# TMS320F28335.net
KiCad netlist of a schematic drawn in Altium Designer
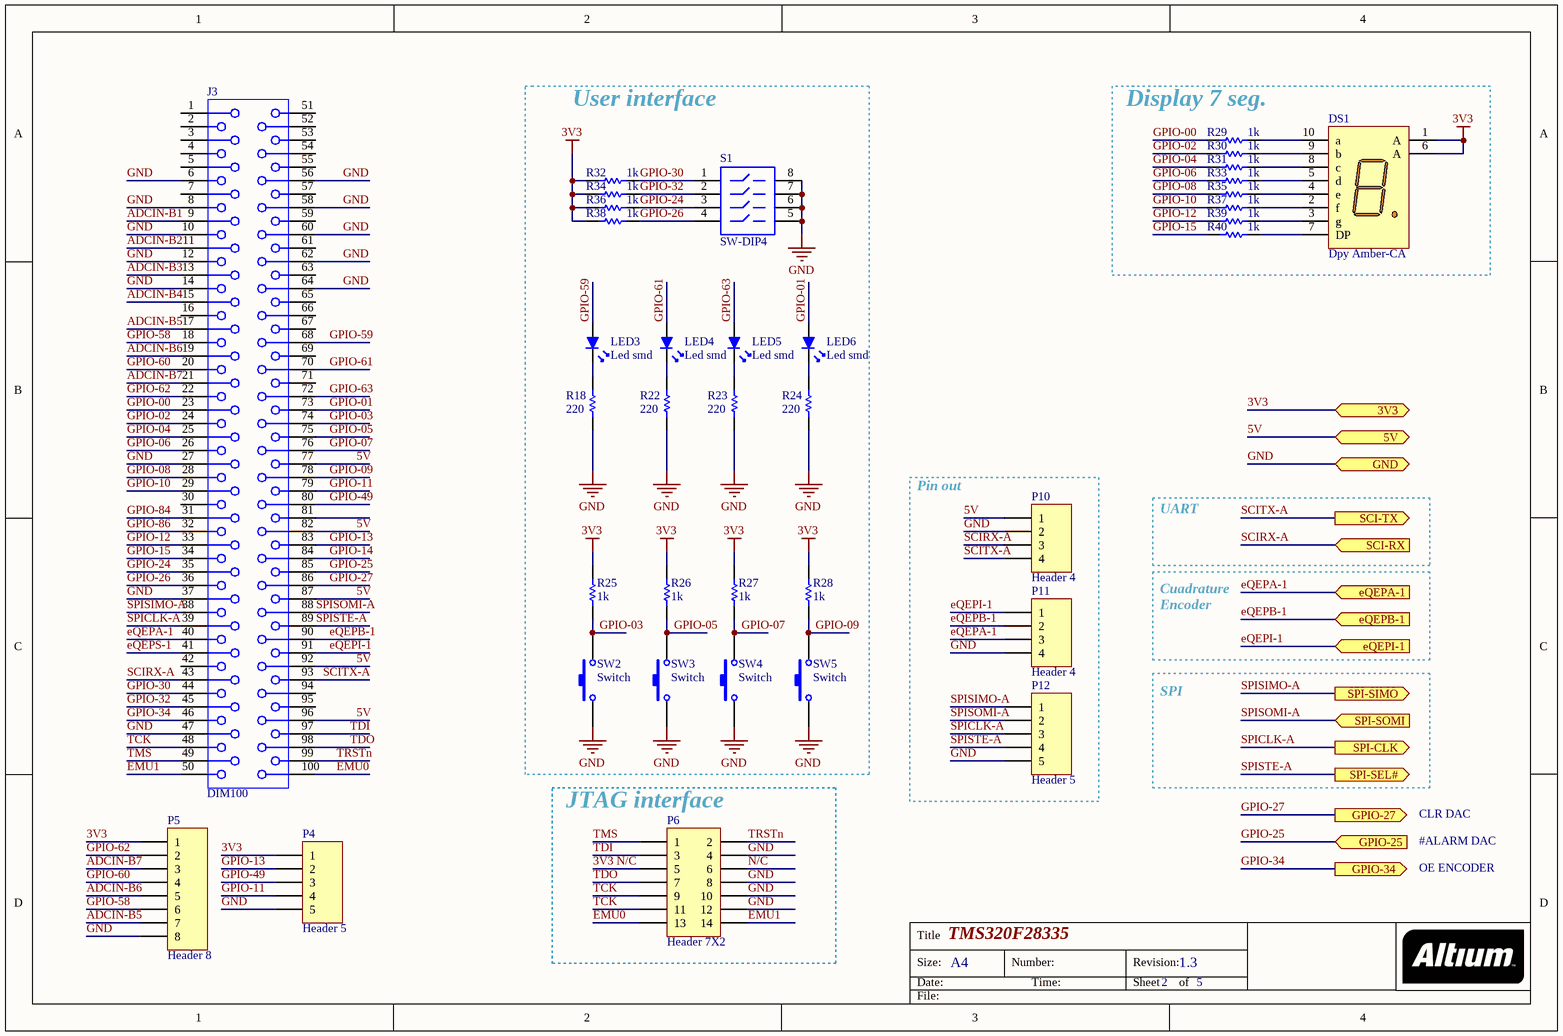
[diagram p0: TMS320F28335.SchDoc]

(export (version "E")
  (design (tool "Eeschema 10.0.6"))
  (components
    (comp (ref "DS1")
      (value "Dpy Amber-CA")
      (footprint "A")
      (description "7.62 mm Black Surface Orange 7-Segment Display: CA, RH DP")
      (fields (field (name "PUBLISHER") "Altium Limited"))
      (libsource (lib "Miscellaneous Devices") (part "Dpy Amber-CA"))
    )
    (comp (ref "J3")
      (value "DIM100")
      (footprint "390213-1")
      (description "Vertical, DIMM 2P Low Insertion Force, 100 Position")
      (fields (field (name "PUBLISHER") "Altium Limited"))
      (libsource (lib "AMP Memory Module DIMM II") (part "390213-1"))
    )
    (comp (ref "LED3")
      (value "Led smd")
      (footprint "LED 1206")
      (description "Led green")
      (fields (field (name ".CREATOR") "SR"))
      (libsource (lib "CDR_SCH") (part "LED"))
    )
    (comp (ref "LED4")
      (value "Led smd")
      (footprint "LED 1206")
      (description "Led yellow")
      (fields (field (name ".CREATOR") "SR"))
      (libsource (lib "CDR_SCH") (part "LED"))
    )
    (comp (ref "LED5")
      (value "Led smd")
      (footprint "LED 1206")
      (description "Led green")
      (fields (field (name ".CREATOR") "SR"))
      (libsource (lib "CDR_SCH") (part "LED"))
    )
    (comp (ref "LED6")
      (value "Led smd")
      (footprint "LED 1206")
      (description "Led yellow")
      (fields (field (name ".CREATOR") "SR"))
      (libsource (lib "CDR_SCH") (part "LED"))
    )
    (comp (ref "P4")
      (value "Header 5")
      (footprint "HDR1X5")
      (description "Header, 5-Pin")
      (fields (field (name "PUBLISHER") "Altium Limited"))
      (libsource (lib "Miscellaneous Connectors") (part "Header 5"))
    )
    (comp (ref "P5")
      (value "Header 8")
      (footprint "HDR1X8")
      (description "Header, 8-Pin")
      (fields (field (name "PUBLISHER") "Altium Limited"))
      (libsource (lib "Miscellaneous Connectors") (part "Header 8"))
    )
    (comp (ref "P6")
      (value "Header 7X2")
      (footprint "HDR2X7")
      (description "Header, 7-Pin, Dual row")
      (fields (field (name "PUBLISHER") "Altium Limited"))
      (libsource (lib "Miscellaneous Connectors") (part "Header 7X2"))
    )
    (comp (ref "P10")
      (value "Header 4")
      (footprint "HDR1X4")
      (description "Header, 4-Pin")
      (fields (field (name "PUBLISHER") "Altium Limited"))
      (libsource (lib "Miscellaneous Connectors") (part "Header 4"))
    )
    (comp (ref "P11")
      (value "Header 4")
      (footprint "HDR1X4")
      (description "Header, 4-Pin")
      (fields (field (name "PUBLISHER") "Altium Limited"))
      (libsource (lib "Miscellaneous Connectors") (part "Header 4"))
    )
    (comp (ref "P12")
      (value "Header 5")
      (footprint "HDR1X5")
      (description "Header, 5-Pin")
      (fields (field (name "PUBLISHER") "Altium Limited"))
      (libsource (lib "Miscellaneous Connectors") (part "Header 5"))
    )
    (comp (ref "R18")
      (value "220")
      (footprint "R 1206")
      (description "Resistencia")
      (fields (field (name "Comment") "R220") (field (name ".CREATOR") "SR"))
      (libsource (lib "CDR_SCH") (part "R"))
    )
    (comp (ref "R22")
      (value "220")
      (footprint "R 1206")
      (description "Resistencia")
      (fields (field (name "Comment") "R220") (field (name ".CREATOR") "SR"))
      (libsource (lib "CDR_SCH") (part "R"))
    )
    (comp (ref "R23")
      (value "220")
      (footprint "R 1206")
      (description "Resistencia")
      (fields (field (name "Comment") "R220") (field (name ".CREATOR") "SR"))
      (libsource (lib "CDR_SCH") (part "R"))
    )
    (comp (ref "R24")
      (value "220")
      (footprint "R 1206")
      (description "Resistencia")
      (fields (field (name "Comment") "R220") (field (name ".CREATOR") "SR"))
      (libsource (lib "CDR_SCH") (part "R"))
    )
    (comp (ref "R25")
      (value "1k")
      (footprint "R 1206")
      (description "Resistencia")
      (fields (field (name "Comment") "R1k") (field (name ".CREATOR") "SR"))
      (libsource (lib "CDR_SCH") (part "R"))
    )
    (comp (ref "R26")
      (value "1k")
      (footprint "R 1206")
      (description "Resistencia")
      (fields (field (name "Comment") "R1k") (field (name ".CREATOR") "SR"))
      (libsource (lib "CDR_SCH") (part "R"))
    )
    (comp (ref "R27")
      (value "1k")
      (footprint "R 1206")
      (description "Resistencia")
      (fields (field (name "Comment") "R1k") (field (name ".CREATOR") "SR"))
      (libsource (lib "CDR_SCH") (part "R"))
    )
    (comp (ref "R28")
      (value "1k")
      (footprint "R 1206")
      (description "Resistencia")
      (fields (field (name "Comment") "R1k") (field (name ".CREATOR") "SR"))
      (libsource (lib "CDR_SCH") (part "R"))
    )
    (comp (ref "R29")
      (value "1k")
      (footprint "R 1206")
      (description "Resistencia")
      (fields (field (name "Comment") "R1k") (field (name ".CREATOR") "SR"))
      (libsource (lib "CDR_SCH") (part "R"))
    )
    (comp (ref "R30")
      (value "1k")
      (footprint "R 1206")
      (description "Resistencia")
      (fields (field (name "Comment") "R1k") (field (name ".CREATOR") "SR"))
      (libsource (lib "CDR_SCH") (part "R"))
    )
    (comp (ref "R31")
      (value "1k")
      (footprint "R 1206")
      (description "Resistencia")
      (fields (field (name "Comment") "R1k") (field (name ".CREATOR") "SR"))
      (libsource (lib "CDR_SCH") (part "R"))
    )
    (comp (ref "R32")
      (value "1k")
      (footprint "R 1206")
      (description "Resistencia")
      (fields (field (name "Comment") "R1k") (field (name ".CREATOR") "SR"))
      (libsource (lib "CDR_SCH") (part "R"))
    )
    (comp (ref "R33")
      (value "1k")
      (footprint "R 1206")
      (description "Resistencia")
      (fields (field (name "Comment") "R1k") (field (name ".CREATOR") "SR"))
      (libsource (lib "CDR_SCH") (part "R"))
    )
    (comp (ref "R34")
      (value "1k")
      (footprint "R 1206")
      (description "Resistencia")
      (fields (field (name "Comment") "R1k") (field (name ".CREATOR") "SR"))
      (libsource (lib "CDR_SCH") (part "R"))
    )
    (comp (ref "R35")
      (value "1k")
      (footprint "R 1206")
      (description "Resistencia")
      (fields (field (name "Comment") "R1k") (field (name ".CREATOR") "SR"))
      (libsource (lib "CDR_SCH") (part "R"))
    )
    (comp (ref "R36")
      (value "1k")
      (footprint "R 1206")
      (description "Resistencia")
      (fields (field (name "Comment") "R1k") (field (name ".CREATOR") "SR"))
      (libsource (lib "CDR_SCH") (part "R"))
    )
    (comp (ref "R37")
      (value "1k")
      (footprint "R 1206")
      (description "Resistencia")
      (fields (field (name "Comment") "R1k") (field (name ".CREATOR") "SR"))
      (libsource (lib "CDR_SCH") (part "R"))
    )
    (comp (ref "R38")
      (value "1k")
      (footprint "R 1206")
      (description "Resistencia")
      (fields (field (name "Comment") "R1k") (field (name ".CREATOR") "SR"))
      (libsource (lib "CDR_SCH") (part "R"))
    )
    (comp (ref "R39")
      (value "1k")
      (footprint "R 1206")
      (description "Resistencia")
      (fields (field (name "Comment") "R1k") (field (name ".CREATOR") "SR"))
      (libsource (lib "CDR_SCH") (part "R"))
    )
    (comp (ref "R40")
      (value "1k")
      (footprint "R 1206")
      (description "Resistencia")
      (fields (field (name "Comment") "R1k") (field (name ".CREATOR") "SR"))
      (libsource (lib "CDR_SCH") (part "R"))
    )
    (comp (ref "S1")
      (value "SW-DIP4")
      (footprint "DIP-8")
      (description "DIP Switch")
      (fields (field (name "PUBLISHER") "Altium Limited"))
      (libsource (lib "Miscellaneous Devices") (part "SW-DIP4"))
    )
    (comp (ref "SW2")
      (value "Switch")
      (footprint "TACT SW")
      (fields (field (name ".CREATOR") "G") (field (name ".PCBCHECK") "G") (field (name ".SCHCHECK") "G"))
      (libsource (lib "CDR_SCH") (part "Pulsador NA 4 term"))
    )
    (comp (ref "SW3")
      (value "Switch")
      (footprint "TACT SW")
      (fields (field (name ".CREATOR") "G") (field (name ".PCBCHECK") "G") (field (name ".SCHCHECK") "G"))
      (libsource (lib "CDR_SCH") (part "Pulsador NA 4 term"))
    )
    (comp (ref "SW4")
      (value "Switch")
      (footprint "TACT SW")
      (fields (field (name ".CREATOR") "G") (field (name ".PCBCHECK") "G") (field (name ".SCHCHECK") "G"))
      (libsource (lib "CDR_SCH") (part "Pulsador NA 4 term"))
    )
    (comp (ref "SW5")
      (value "Switch")
      (footprint "TACT SW")
      (fields (field (name ".CREATOR") "G") (field (name ".PCBCHECK") "G") (field (name ".SCHCHECK") "G"))
      (libsource (lib "CDR_SCH") (part "Pulsador NA 4 term"))
    )
  )
  (nets
    (net (code "1") (name "/3V3 N{slash}C") (class "Default")
      (node (ref "P6") (pin "5") (pinfunction "5_5") (pintype "passive"))
    )
    (net (code "2") (name "/5V") (class "Default")
      (node (ref "J3") (pin "77") (pinfunction "p77_77") (pintype "passive"))
      (node (ref "J3") (pin "82") (pinfunction "p82_82") (pintype "passive"))
      (node (ref "J3") (pin "87") (pinfunction "p87_87") (pintype "passive"))
      (node (ref "J3") (pin "92") (pinfunction "p92_92") (pintype "passive"))
      (node (ref "J3") (pin "96") (pinfunction "p96_96") (pintype "passive"))
      (node (ref "P10") (pin "1") (pinfunction "1_1") (pintype "passive"))
    )
    (net (code "3") (name "/ADCIN-B1") (class "Default")
      (node (ref "J3") (pin "9") (pinfunction "p9_9") (pintype "passive"))
    )
    (net (code "4") (name "/ADCIN-B2") (class "Default")
      (node (ref "J3") (pin "11") (pinfunction "p11_11") (pintype "passive"))
    )
    (net (code "5") (name "/ADCIN-B3") (class "Default")
      (node (ref "J3") (pin "13") (pinfunction "p13_13") (pintype "passive"))
    )
    (net (code "6") (name "/ADCIN-B4") (class "Default")
      (node (ref "J3") (pin "15") (pinfunction "p15_15") (pintype "passive"))
    )
    (net (code "7") (name "/ADCIN-B5") (class "Default")
      (node (ref "J3") (pin "17") (pinfunction "p17_17") (pintype "passive"))
      (node (ref "P5") (pin "7") (pinfunction "7_7") (pintype "passive"))
    )
    (net (code "8") (name "/ADCIN-B6") (class "Default")
      (node (ref "J3") (pin "19") (pinfunction "p19_19") (pintype "passive"))
      (node (ref "P5") (pin "5") (pinfunction "5_5") (pintype "passive"))
    )
    (net (code "9") (name "/ADCIN-B7") (class "Default")
      (node (ref "J3") (pin "21") (pinfunction "p21_21") (pintype "passive"))
      (node (ref "P5") (pin "3") (pinfunction "3_3") (pintype "passive"))
    )
    (net (code "10") (name "/EMU0") (class "Default")
      (node (ref "J3") (pin "100") (pinfunction "p100_100") (pintype "passive"))
      (node (ref "P6") (pin "13") (pinfunction "13_13") (pintype "passive"))
    )
    (net (code "11") (name "/EMU1") (class "Default")
      (node (ref "J3") (pin "50") (pinfunction "p50_50") (pintype "passive"))
      (node (ref "P6") (pin "14") (pinfunction "14_14") (pintype "passive"))
    )
    (net (code "12") (name "/GPIO-00") (class "Default")
      (node (ref "J3") (pin "23") (pinfunction "p23_23") (pintype "passive"))
      (node (ref "R29") (pin "1") (pinfunction "1_1") (pintype "passive"))
    )
    (net (code "13") (name "/GPIO-01") (class "Default")
      (node (ref "J3") (pin "73") (pinfunction "p73_73") (pintype "passive"))
      (node (ref "LED6") (pin "1") (pinfunction "A_1") (pintype "passive"))
    )
    (net (code "14") (name "/GPIO-02") (class "Default")
      (node (ref "J3") (pin "24") (pinfunction "p24_24") (pintype "passive"))
      (node (ref "R30") (pin "1") (pinfunction "1_1") (pintype "passive"))
    )
    (net (code "15") (name "/GPIO-03") (class "Default")
      (node (ref "J3") (pin "74") (pinfunction "p74_74") (pintype "passive"))
      (node (ref "R25") (pin "1") (pinfunction "1_1") (pintype "passive"))
      (node (ref "SW2") (pin "2") (pinfunction "2_2") (pintype "passive"))
    )
    (net (code "16") (name "/GPIO-04") (class "Default")
      (node (ref "J3") (pin "25") (pinfunction "p25_25") (pintype "passive"))
      (node (ref "R31") (pin "1") (pinfunction "1_1") (pintype "passive"))
    )
    (net (code "17") (name "/GPIO-05") (class "Default")
      (node (ref "J3") (pin "75") (pinfunction "p75_75") (pintype "passive"))
      (node (ref "R26") (pin "1") (pinfunction "1_1") (pintype "passive"))
      (node (ref "SW3") (pin "2") (pinfunction "2_2") (pintype "passive"))
    )
    (net (code "18") (name "/GPIO-06") (class "Default")
      (node (ref "J3") (pin "26") (pinfunction "p26_26") (pintype "passive"))
      (node (ref "R33") (pin "1") (pinfunction "1_1") (pintype "passive"))
    )
    (net (code "19") (name "/GPIO-07") (class "Default")
      (node (ref "J3") (pin "76") (pinfunction "p76_76") (pintype "passive"))
      (node (ref "R27") (pin "1") (pinfunction "1_1") (pintype "passive"))
      (node (ref "SW4") (pin "2") (pinfunction "2_2") (pintype "passive"))
    )
    (net (code "20") (name "/GPIO-08") (class "Default")
      (node (ref "J3") (pin "28") (pinfunction "p28_28") (pintype "passive"))
      (node (ref "R35") (pin "1") (pinfunction "1_1") (pintype "passive"))
    )
    (net (code "21") (name "/GPIO-09") (class "Default")
      (node (ref "J3") (pin "78") (pinfunction "p78_78") (pintype "passive"))
      (node (ref "R28") (pin "1") (pinfunction "1_1") (pintype "passive"))
      (node (ref "SW5") (pin "2") (pinfunction "2_2") (pintype "passive"))
    )
    (net (code "22") (name "/GPIO-10") (class "Default")
      (node (ref "J3") (pin "29") (pinfunction "p29_29") (pintype "passive"))
      (node (ref "R37") (pin "1") (pinfunction "1_1") (pintype "passive"))
    )
    (net (code "23") (name "/GPIO-11") (class "Default")
      (node (ref "J3") (pin "79") (pinfunction "p79_79") (pintype "passive"))
      (node (ref "P4") (pin "4") (pinfunction "4_4") (pintype "passive"))
    )
    (net (code "24") (name "/GPIO-12") (class "Default")
      (node (ref "J3") (pin "33") (pinfunction "p33_33") (pintype "passive"))
      (node (ref "R39") (pin "1") (pinfunction "1_1") (pintype "passive"))
    )
    (net (code "25") (name "/GPIO-13") (class "Default")
      (node (ref "J3") (pin "83") (pinfunction "p83_83") (pintype "passive"))
      (node (ref "P4") (pin "2") (pinfunction "2_2") (pintype "passive"))
    )
    (net (code "26") (name "/GPIO-14") (class "Default")
      (node (ref "J3") (pin "84") (pinfunction "p84_84") (pintype "passive"))
    )
    (net (code "27") (name "/GPIO-15") (class "Default")
      (node (ref "J3") (pin "34") (pinfunction "p34_34") (pintype "passive"))
      (node (ref "R40") (pin "1") (pinfunction "1_1") (pintype "passive"))
    )
    (net (code "28") (name "/GPIO-24") (class "Default")
      (node (ref "J3") (pin "35") (pinfunction "p35_35") (pintype "passive"))
      (node (ref "R36") (pin "2") (pinfunction "2_2") (pintype "passive"))
      (node (ref "S1") (pin "3") (pinfunction "3_3") (pintype "passive"))
    )
    (net (code "29") (name "/GPIO-25") (class "Default")
      (node (ref "J3") (pin "85") (pinfunction "p85_85") (pintype "passive"))
    )
    (net (code "30") (name "/GPIO-26") (class "Default")
      (node (ref "J3") (pin "36") (pinfunction "p36_36") (pintype "passive"))
      (node (ref "R38") (pin "2") (pinfunction "2_2") (pintype "passive"))
      (node (ref "S1") (pin "4") (pinfunction "4_4") (pintype "passive"))
    )
    (net (code "31") (name "/GPIO-27") (class "Default")
      (node (ref "J3") (pin "86") (pinfunction "p86_86") (pintype "passive"))
    )
    (net (code "32") (name "/GPIO-30") (class "Default")
      (node (ref "J3") (pin "44") (pinfunction "p44_44") (pintype "passive"))
      (node (ref "R32") (pin "2") (pinfunction "2_2") (pintype "passive"))
      (node (ref "S1") (pin "1") (pinfunction "1_1") (pintype "passive"))
    )
    (net (code "33") (name "/GPIO-32") (class "Default")
      (node (ref "J3") (pin "45") (pinfunction "p45_45") (pintype "passive"))
      (node (ref "R34") (pin "2") (pinfunction "2_2") (pintype "passive"))
      (node (ref "S1") (pin "2") (pinfunction "2_2") (pintype "passive"))
    )
    (net (code "34") (name "/GPIO-34") (class "Default")
      (node (ref "J3") (pin "46") (pinfunction "p46_46") (pintype "passive"))
    )
    (net (code "35") (name "/GPIO-49") (class "Default")
      (node (ref "J3") (pin "80") (pinfunction "p80_80") (pintype "passive"))
      (node (ref "P4") (pin "3") (pinfunction "3_3") (pintype "passive"))
    )
    (net (code "36") (name "/GPIO-58") (class "Default")
      (node (ref "J3") (pin "18") (pinfunction "p18_18") (pintype "passive"))
      (node (ref "P5") (pin "6") (pinfunction "6_6") (pintype "passive"))
    )
    (net (code "37") (name "/GPIO-59") (class "Default")
      (node (ref "J3") (pin "68") (pinfunction "p68_68") (pintype "passive"))
      (node (ref "LED3") (pin "1") (pinfunction "A_1") (pintype "passive"))
    )
    (net (code "38") (name "/GPIO-60") (class "Default")
      (node (ref "J3") (pin "20") (pinfunction "p20_20") (pintype "passive"))
      (node (ref "P5") (pin "4") (pinfunction "4_4") (pintype "passive"))
    )
    (net (code "39") (name "/GPIO-61") (class "Default")
      (node (ref "J3") (pin "70") (pinfunction "p70_70") (pintype "passive"))
      (node (ref "LED4") (pin "1") (pinfunction "A_1") (pintype "passive"))
    )
    (net (code "40") (name "/GPIO-62") (class "Default")
      (node (ref "J3") (pin "22") (pinfunction "p22_22") (pintype "passive"))
      (node (ref "P5") (pin "2") (pinfunction "2_2") (pintype "passive"))
    )
    (net (code "41") (name "/GPIO-63") (class "Default")
      (node (ref "J3") (pin "72") (pinfunction "p72_72") (pintype "passive"))
      (node (ref "LED5") (pin "1") (pinfunction "A_1") (pintype "passive"))
    )
    (net (code "42") (name "/GPIO-84") (class "Default")
      (node (ref "J3") (pin "31") (pinfunction "p31_31") (pintype "passive"))
    )
    (net (code "43") (name "/GPIO-86") (class "Default")
      (node (ref "J3") (pin "32") (pinfunction "p32_32") (pintype "passive"))
    )
    (net (code "44") (name "/N{slash}C") (class "Default")
      (node (ref "P6") (pin "6") (pinfunction "6_6") (pintype "passive"))
    )
    (net (code "45") (name "/SCIRX-A") (class "Default")
      (node (ref "J3") (pin "43") (pinfunction "p43_43") (pintype "passive"))
      (node (ref "P10") (pin "3") (pinfunction "3_3") (pintype "passive"))
    )
    (net (code "46") (name "/SCITX-A") (class "Default")
      (node (ref "J3") (pin "93") (pinfunction "p93_93") (pintype "passive"))
      (node (ref "P10") (pin "4") (pinfunction "4_4") (pintype "passive"))
    )
    (net (code "47") (name "/SPICLK-A") (class "Default")
      (node (ref "J3") (pin "39") (pinfunction "p39_39") (pintype "passive"))
      (node (ref "P12") (pin "3") (pinfunction "3_3") (pintype "passive"))
    )
    (net (code "48") (name "/SPISIMO-A") (class "Default")
      (node (ref "J3") (pin "38") (pinfunction "p38_38") (pintype "passive"))
      (node (ref "P12") (pin "1") (pinfunction "1_1") (pintype "passive"))
    )
    (net (code "49") (name "/SPISOMI-A") (class "Default")
      (node (ref "J3") (pin "88") (pinfunction "p88_88") (pintype "passive"))
      (node (ref "P12") (pin "2") (pinfunction "2_2") (pintype "passive"))
    )
    (net (code "50") (name "/SPISTE-A") (class "Default")
      (node (ref "J3") (pin "89") (pinfunction "p89_89") (pintype "passive"))
      (node (ref "P12") (pin "4") (pinfunction "4_4") (pintype "passive"))
    )
    (net (code "51") (name "/TCK") (class "Default")
      (node (ref "J3") (pin "48") (pinfunction "p48_48") (pintype "passive"))
      (node (ref "P6") (pin "11") (pinfunction "11_11") (pintype "passive"))
      (node (ref "P6") (pin "9") (pinfunction "9_9") (pintype "passive"))
    )
    (net (code "52") (name "/TDI") (class "Default")
      (node (ref "J3") (pin "97") (pinfunction "p97_97") (pintype "passive"))
      (node (ref "P6") (pin "3") (pinfunction "3_3") (pintype "passive"))
    )
    (net (code "53") (name "/TDO") (class "Default")
      (node (ref "J3") (pin "98") (pinfunction "p98_98") (pintype "passive"))
      (node (ref "P6") (pin "7") (pinfunction "7_7") (pintype "passive"))
    )
    (net (code "54") (name "/TMS") (class "Default")
      (node (ref "J3") (pin "49") (pinfunction "p49_49") (pintype "passive"))
      (node (ref "P6") (pin "1") (pinfunction "1_1") (pintype "passive"))
    )
    (net (code "55") (name "/TRSTn") (class "Default")
      (node (ref "J3") (pin "99") (pinfunction "p99_99") (pintype "passive"))
      (node (ref "P6") (pin "2") (pinfunction "2_2") (pintype "passive"))
    )
    (net (code "56") (name "/eQEPA-1") (class "Default")
      (node (ref "J3") (pin "40") (pinfunction "p40_40") (pintype "passive"))
      (node (ref "P11") (pin "3") (pinfunction "3_3") (pintype "passive"))
    )
    (net (code "57") (name "/eQEPB-1") (class "Default")
      (node (ref "J3") (pin "90") (pinfunction "p90_90") (pintype "passive"))
      (node (ref "P11") (pin "2") (pinfunction "2_2") (pintype "passive"))
    )
    (net (code "58") (name "/eQEPI-1") (class "Default")
      (node (ref "J3") (pin "91") (pinfunction "p91_91") (pintype "passive"))
      (node (ref "P11") (pin "1") (pinfunction "1_1") (pintype "passive"))
    )
    (net (code "59") (name "/eQEPS-1") (class "Default")
      (node (ref "J3") (pin "41") (pinfunction "p41_41") (pintype "passive"))
    )
    (net (code "60") (name "3V3") (class "Default")
      (node (ref "DS1") (pin "1") (pinfunction "A_1") (pintype "passive"))
      (node (ref "DS1") (pin "6") (pinfunction "A_6") (pintype "passive"))
      (node (ref "P4") (pin "1") (pinfunction "1_1") (pintype "passive"))
      (node (ref "P5") (pin "1") (pinfunction "1_1") (pintype "passive"))
      (node (ref "R25") (pin "2") (pinfunction "2_2") (pintype "passive"))
      (node (ref "R26") (pin "2") (pinfunction "2_2") (pintype "passive"))
      (node (ref "R27") (pin "2") (pinfunction "2_2") (pintype "passive"))
      (node (ref "R28") (pin "2") (pinfunction "2_2") (pintype "passive"))
      (node (ref "R32") (pin "1") (pinfunction "1_1") (pintype "passive"))
      (node (ref "R34") (pin "1") (pinfunction "1_1") (pintype "passive"))
      (node (ref "R36") (pin "1") (pinfunction "1_1") (pintype "passive"))
      (node (ref "R38") (pin "1") (pinfunction "1_1") (pintype "passive"))
    )
    (net (code "61") (name "GND") (class "Default")
      (node (ref "J3") (pin "10") (pinfunction "p10_10") (pintype "passive"))
      (node (ref "J3") (pin "12") (pinfunction "p12_12") (pintype "passive"))
      (node (ref "J3") (pin "14") (pinfunction "p14_14") (pintype "passive"))
      (node (ref "J3") (pin "27") (pinfunction "p27_27") (pintype "passive"))
      (node (ref "J3") (pin "37") (pinfunction "p37_37") (pintype "passive"))
      (node (ref "J3") (pin "47") (pinfunction "p47_47") (pintype "passive"))
      (node (ref "J3") (pin "56") (pinfunction "p56_56") (pintype "passive"))
      (node (ref "J3") (pin "58") (pinfunction "p58_58") (pintype "passive"))
      (node (ref "J3") (pin "6") (pinfunction "p6_6") (pintype "passive"))
      (node (ref "J3") (pin "60") (pinfunction "p60_60") (pintype "passive"))
      (node (ref "J3") (pin "62") (pinfunction "p62_62") (pintype "passive"))
      (node (ref "J3") (pin "64") (pinfunction "p64_64") (pintype "passive"))
      (node (ref "J3") (pin "8") (pinfunction "p8_8") (pintype "passive"))
      (node (ref "P10") (pin "2") (pinfunction "2_2") (pintype "passive"))
      (node (ref "P11") (pin "4") (pinfunction "4_4") (pintype "passive"))
      (node (ref "P12") (pin "5") (pinfunction "5_5") (pintype "passive"))
      (node (ref "P4") (pin "5") (pinfunction "5_5") (pintype "passive"))
      (node (ref "P5") (pin "8") (pinfunction "8_8") (pintype "passive"))
      (node (ref "P6") (pin "10") (pinfunction "10_10") (pintype "passive"))
      (node (ref "P6") (pin "12") (pinfunction "12_12") (pintype "passive"))
      (node (ref "P6") (pin "4") (pinfunction "4_4") (pintype "passive"))
      (node (ref "P6") (pin "8") (pinfunction "8_8") (pintype "passive"))
      (node (ref "R18") (pin "2") (pinfunction "2_2") (pintype "passive"))
      (node (ref "R22") (pin "2") (pinfunction "2_2") (pintype "passive"))
      (node (ref "R23") (pin "2") (pinfunction "2_2") (pintype "passive"))
      (node (ref "R24") (pin "2") (pinfunction "2_2") (pintype "passive"))
      (node (ref "S1") (pin "5") (pinfunction "5_5") (pintype "passive"))
      (node (ref "S1") (pin "6") (pinfunction "6_6") (pintype "passive"))
      (node (ref "S1") (pin "7") (pinfunction "7_7") (pintype "passive"))
      (node (ref "S1") (pin "8") (pinfunction "8_8") (pintype "passive"))
      (node (ref "SW2") (pin "1") (pinfunction "1_1") (pintype "passive"))
      (node (ref "SW3") (pin "1") (pinfunction "1_1") (pintype "passive"))
      (node (ref "SW4") (pin "1") (pinfunction "1_1") (pintype "passive"))
      (node (ref "SW5") (pin "1") (pinfunction "1_1") (pintype "passive"))
    )
    (net (code "62") (name "Net-(DS1-DP)") (class "Default")
      (node (ref "DS1") (pin "7") (pinfunction "DP_7") (pintype "passive"))
      (node (ref "R40") (pin "2") (pinfunction "2_2") (pintype "passive"))
    )
    (net (code "63") (name "Net-(DS1-a)") (class "Default")
      (node (ref "DS1") (pin "10") (pinfunction "a_10") (pintype "passive"))
      (node (ref "R29") (pin "2") (pinfunction "2_2") (pintype "passive"))
    )
    (net (code "64") (name "Net-(DS1-b)") (class "Default")
      (node (ref "DS1") (pin "9") (pinfunction "b_9") (pintype "passive"))
      (node (ref "R30") (pin "2") (pinfunction "2_2") (pintype "passive"))
    )
    (net (code "65") (name "Net-(DS1-c)") (class "Default")
      (node (ref "DS1") (pin "8") (pinfunction "c_8") (pintype "passive"))
      (node (ref "R31") (pin "2") (pinfunction "2_2") (pintype "passive"))
    )
    (net (code "66") (name "Net-(DS1-d)") (class "Default")
      (node (ref "DS1") (pin "5") (pinfunction "d_5") (pintype "passive"))
      (node (ref "R33") (pin "2") (pinfunction "2_2") (pintype "passive"))
    )
    (net (code "67") (name "Net-(DS1-e)") (class "Default")
      (node (ref "DS1") (pin "4") (pinfunction "e_4") (pintype "passive"))
      (node (ref "R35") (pin "2") (pinfunction "2_2") (pintype "passive"))
    )
    (net (code "68") (name "Net-(DS1-f)") (class "Default")
      (node (ref "DS1") (pin "2") (pinfunction "f_2") (pintype "passive"))
      (node (ref "R37") (pin "2") (pinfunction "2_2") (pintype "passive"))
    )
    (net (code "69") (name "Net-(DS1-g)") (class "Default")
      (node (ref "DS1") (pin "3") (pinfunction "g_3") (pintype "passive"))
      (node (ref "R39") (pin "2") (pinfunction "2_2") (pintype "passive"))
    )
    (net (code "70") (name "Net-(LED3-K)") (class "Default")
      (node (ref "LED3") (pin "2") (pinfunction "K_2") (pintype "passive"))
      (node (ref "R18") (pin "1") (pinfunction "1_1") (pintype "passive"))
    )
    (net (code "71") (name "Net-(LED4-K)") (class "Default")
      (node (ref "LED4") (pin "2") (pinfunction "K_2") (pintype "passive"))
      (node (ref "R22") (pin "1") (pinfunction "1_1") (pintype "passive"))
    )
    (net (code "72") (name "Net-(LED5-K)") (class "Default")
      (node (ref "LED5") (pin "2") (pinfunction "K_2") (pintype "passive"))
      (node (ref "R23") (pin "1") (pinfunction "1_1") (pintype "passive"))
    )
    (net (code "73") (name "Net-(LED6-K)") (class "Default")
      (node (ref "LED6") (pin "2") (pinfunction "K_2") (pintype "passive"))
      (node (ref "R24") (pin "1") (pinfunction "1_1") (pintype "passive"))
    )
    (net (code "74") (name "unconnected-(J3-p1-Pad1)") (class "Default")
      (node (ref "J3") (pin "1") (pinfunction "p1_1") (pintype "passive"))
    )
    (net (code "75") (name "unconnected-(J3-p2-Pad2)") (class "Default")
      (node (ref "J3") (pin "2") (pinfunction "p2_2") (pintype "passive"))
    )
    (net (code "76") (name "unconnected-(J3-p3-Pad3)") (class "Default")
      (node (ref "J3") (pin "3") (pinfunction "p3_3") (pintype "passive"))
    )
    (net (code "77") (name "unconnected-(J3-p4-Pad4)") (class "Default")
      (node (ref "J3") (pin "4") (pinfunction "p4_4") (pintype "passive"))
    )
    (net (code "78") (name "unconnected-(J3-p5-Pad5)") (class "Default")
      (node (ref "J3") (pin "5") (pinfunction "p5_5") (pintype "passive"))
    )
    (net (code "79") (name "unconnected-(J3-p7-Pad7)") (class "Default")
      (node (ref "J3") (pin "7") (pinfunction "p7_7") (pintype "passive"))
    )
    (net (code "80") (name "unconnected-(J3-p16-Pad16)") (class "Default")
      (node (ref "J3") (pin "16") (pinfunction "p16_16") (pintype "passive"))
    )
    (net (code "81") (name "unconnected-(J3-p30-Pad30)") (class "Default")
      (node (ref "J3") (pin "30") (pinfunction "p30_30") (pintype "passive"))
    )
    (net (code "82") (name "unconnected-(J3-p42-Pad42)") (class "Default")
      (node (ref "J3") (pin "42") (pinfunction "p42_42") (pintype "passive"))
    )
    (net (code "83") (name "unconnected-(J3-p51-Pad51)") (class "Default")
      (node (ref "J3") (pin "51") (pinfunction "p51_51") (pintype "passive"))
    )
    (net (code "84") (name "unconnected-(J3-p52-Pad52)") (class "Default")
      (node (ref "J3") (pin "52") (pinfunction "p52_52") (pintype "passive"))
    )
    (net (code "85") (name "unconnected-(J3-p53-Pad53)") (class "Default")
      (node (ref "J3") (pin "53") (pinfunction "p53_53") (pintype "passive"))
    )
    (net (code "86") (name "unconnected-(J3-p54-Pad54)") (class "Default")
      (node (ref "J3") (pin "54") (pinfunction "p54_54") (pintype "passive"))
    )
    (net (code "87") (name "unconnected-(J3-p55-Pad55)") (class "Default")
      (node (ref "J3") (pin "55") (pinfunction "p55_55") (pintype "passive"))
    )
    (net (code "88") (name "unconnected-(J3-p57-Pad57)") (class "Default")
      (node (ref "J3") (pin "57") (pinfunction "p57_57") (pintype "passive"))
    )
    (net (code "89") (name "unconnected-(J3-p59-Pad59)") (class "Default")
      (node (ref "J3") (pin "59") (pinfunction "p59_59") (pintype "passive"))
    )
    (net (code "90") (name "unconnected-(J3-p61-Pad61)") (class "Default")
      (node (ref "J3") (pin "61") (pinfunction "p61_61") (pintype "passive"))
    )
    (net (code "91") (name "unconnected-(J3-p63-Pad63)") (class "Default")
      (node (ref "J3") (pin "63") (pinfunction "p63_63") (pintype "passive"))
    )
    (net (code "92") (name "unconnected-(J3-p65-Pad65)") (class "Default")
      (node (ref "J3") (pin "65") (pinfunction "p65_65") (pintype "passive"))
    )
    (net (code "93") (name "unconnected-(J3-p66-Pad66)") (class "Default")
      (node (ref "J3") (pin "66") (pinfunction "p66_66") (pintype "passive"))
    )
    (net (code "94") (name "unconnected-(J3-p67-Pad67)") (class "Default")
      (node (ref "J3") (pin "67") (pinfunction "p67_67") (pintype "passive"))
    )
    (net (code "95") (name "unconnected-(J3-p69-Pad69)") (class "Default")
      (node (ref "J3") (pin "69") (pinfunction "p69_69") (pintype "passive"))
    )
    (net (code "96") (name "unconnected-(J3-p71-Pad71)") (class "Default")
      (node (ref "J3") (pin "71") (pinfunction "p71_71") (pintype "passive"))
    )
    (net (code "97") (name "unconnected-(J3-p81-Pad81)") (class "Default")
      (node (ref "J3") (pin "81") (pinfunction "p81_81") (pintype "passive"))
    )
    (net (code "98") (name "unconnected-(J3-p94-Pad94)") (class "Default")
      (node (ref "J3") (pin "94") (pinfunction "p94_94") (pintype "passive"))
    )
    (net (code "99") (name "unconnected-(J3-p95-Pad95)") (class "Default")
      (node (ref "J3") (pin "95") (pinfunction "p95_95") (pintype "passive"))
    )
  )
)
